# Main.net
KiCad netlist of a schematic drawn in Altium Designer
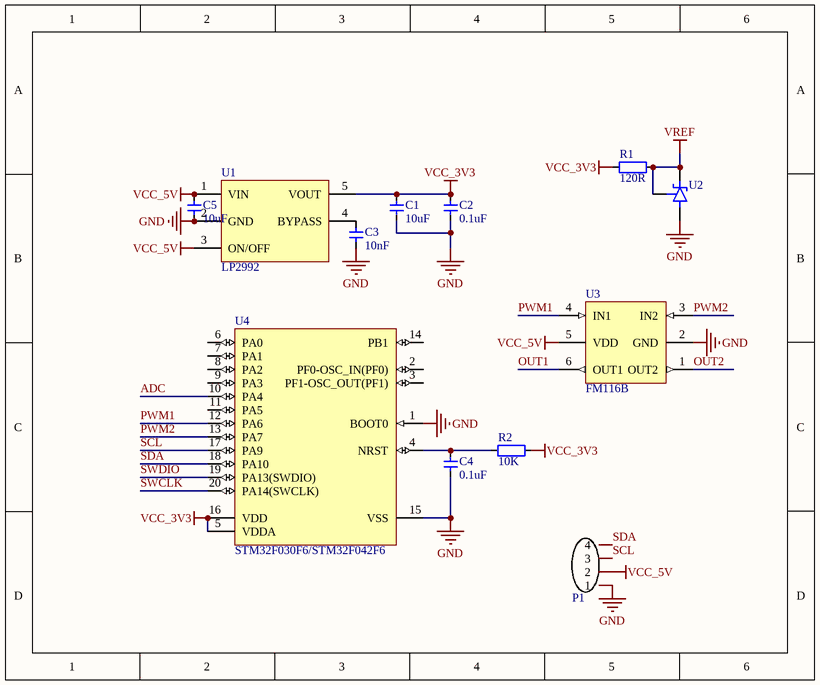
[diagram p0: Main.SchDoc]

(export (version "E")
  (design (tool "Eeschema 10.0.6"))
  (components
    (comp (ref "C1")
      (value "10uF")
      (footprint "ServoDrive:CAP_0402")
      (description "Capacitor")
      (libsource (lib "MyPcbLib") (part "电容-0402"))
    )
    (comp (ref "C2")
      (value "0.1uF")
      (footprint "ServoDrive:CAP_0402")
      (description "Capacitor")
      (libsource (lib "MyPcbLib") (part "电容-0402"))
    )
    (comp (ref "C3")
      (value "10nF")
      (footprint "ServoDrive:CAP_0402")
      (description "Capacitor")
      (libsource (lib "MyPcbLib") (part "电容-0402"))
    )
    (comp (ref "C4")
      (value "0.1uF")
      (footprint "ServoDrive:CAP_0402")
      (description "Capacitor")
      (libsource (lib "MyPcbLib") (part "电容-0402"))
    )
    (comp (ref "C5")
      (value "10uF")
      (footprint "ServoDrive:CAP_0402")
      (description "Capacitor")
      (libsource (lib "MyPcbLib") (part "电容-0402"))
    )
    (comp (ref "P1")
      (value "HDR1x4_1.27")
      (footprint "ServoDrive:HDR1X4_1.27_180")
      (description "Header")
      (libsource (lib "altium-import") (part "root_2_HDR1x4_1.27_"))
    )
    (comp (ref "R1")
      (value "120R")
      (footprint "ServoDrive:RES_0402")
      (description "Resistor")
      (libsource (lib "MyPcbLib") (part "电阻-0402"))
    )
    (comp (ref "R2")
      (value "10K")
      (footprint "ServoDrive:RES_0402")
      (description "Resistor")
      (libsource (lib "") (part "电阻-0402_1"))
    )
    (comp (ref "U1")
      (value "LP2992")
      (footprint "ServoDrive:SOT23-5")
      (description "LDO")
      (libsource (lib "MyPcbLib") (part "LP2992"))
    )
    (comp (ref "U2")
      (value "TL431IDBZT")
      (footprint "ServoDrive:SOT23-3")
      (description "Adjustable precision shunt regulator 3-SOT-23 -40 to 85")
      (fields (field (name "MF") "Texas Instruments"))
      (libsource (lib "MyPcbLib") (part "TL431IDBZT"))
    )
    (comp (ref "U3")
      (value "FM116B")
      (footprint "ServoDrive:SOT23-6")
      (fields (field (name "PARTNUMBER") "24LC256-I/ST"))
      (libsource (lib "MyPcbLib") (part "FM116B"))
    )
    (comp (ref "U4")
      (value "STM32F030F6/STM32F042F6")
      (footprint "ServoDrive:TSSOP-20")
      (fields (field (name "PARTNUMBER") "STM32F030F4P6"))
      (libsource (lib "MyPcbLib") (part "STM32F030F4P6"))
    )
  )
  (nets
    (net (code "1") (name "/ADC") (class "Default")
      (node (ref "U4") (pin "10") (pinfunction "PA4_10") (pintype "bidirectional"))
    )
    (net (code "2") (name "/OUT1") (class "Default")
      (node (ref "U3") (pin "6") (pinfunction "OUT1_6") (pintype "output"))
    )
    (net (code "3") (name "/OUT2") (class "Default")
      (node (ref "U3") (pin "1") (pinfunction "OUT2_1") (pintype "output"))
    )
    (net (code "4") (name "/PWM1") (class "Default")
      (node (ref "U3") (pin "4") (pinfunction "IN1_4") (pintype "input"))
      (node (ref "U4") (pin "12") (pinfunction "PA6_12") (pintype "bidirectional"))
    )
    (net (code "5") (name "/PWM2") (class "Default")
      (node (ref "U3") (pin "3") (pinfunction "IN2_3") (pintype "input"))
      (node (ref "U4") (pin "13") (pinfunction "PA7_13") (pintype "bidirectional"))
    )
    (net (code "6") (name "/SCL") (class "Default")
      (node (ref "P1") (pin "3") (pinfunction "3_3") (pintype "passive"))
      (node (ref "U4") (pin "17") (pinfunction "PA9_17") (pintype "bidirectional"))
    )
    (net (code "7") (name "/SDA") (class "Default")
      (node (ref "P1") (pin "4") (pinfunction "4_4") (pintype "passive"))
      (node (ref "U4") (pin "18") (pinfunction "PA10_18") (pintype "bidirectional"))
    )
    (net (code "8") (name "/SWCLK") (class "Default")
      (node (ref "U4") (pin "20") (pinfunction "PA14(SWCLK)_20") (pintype "bidirectional"))
    )
    (net (code "9") (name "/SWDIO") (class "Default")
      (node (ref "U4") (pin "19") (pinfunction "PA13(SWDIO)_19") (pintype "bidirectional"))
    )
    (net (code "10") (name "GND") (class "Default")
      (node (ref "C1") (pin "1") (pinfunction "1_1") (pintype "passive"))
      (node (ref "C2") (pin "1") (pinfunction "1_1") (pintype "passive"))
      (node (ref "C3") (pin "2") (pinfunction "2_2") (pintype "passive"))
      (node (ref "C4") (pin "1") (pinfunction "1_1") (pintype "passive"))
      (node (ref "C5") (pin "1") (pinfunction "1_1") (pintype "passive"))
      (node (ref "P1") (pin "1") (pinfunction "1_1") (pintype "passive"))
      (node (ref "U1") (pin "2") (pinfunction "GND_2") (pintype "passive"))
      (node (ref "U2") (pin "3") (pinfunction "ANODE_3") (pintype "passive"))
      (node (ref "U3") (pin "2") (pinfunction "GND_2") (pintype "power_in"))
      (node (ref "U4") (pin "1") (pinfunction "BOOT0_1") (pintype "input"))
      (node (ref "U4") (pin "15") (pinfunction "VSS_15") (pintype "power_in"))
    )
    (net (code "11") (name "Net-(U1-BYPASS)") (class "Default")
      (node (ref "C3") (pin "1") (pinfunction "1_1") (pintype "passive"))
      (node (ref "U1") (pin "4") (pinfunction "BYPASS_4") (pintype "passive"))
    )
    (net (code "12") (name "Net-(U4-NRST)") (class "Default")
      (node (ref "C4") (pin "2") (pinfunction "2_2") (pintype "passive"))
      (node (ref "R2") (pin "2") (pinfunction "2_2") (pintype "passive"))
      (node (ref "U4") (pin "4") (pinfunction "NRST_4") (pintype "bidirectional"))
    )
    (net (code "13") (name "VCC_3V3") (class "Default")
      (node (ref "C1") (pin "2") (pinfunction "2_2") (pintype "passive"))
      (node (ref "C2") (pin "2") (pinfunction "2_2") (pintype "passive"))
      (node (ref "R1") (pin "1") (pinfunction "1_1") (pintype "passive"))
      (node (ref "R2") (pin "1") (pinfunction "1_1") (pintype "passive"))
      (node (ref "U1") (pin "5") (pinfunction "VOUT_5") (pintype "passive"))
      (node (ref "U4") (pin "16") (pinfunction "VDD_16") (pintype "power_in"))
      (node (ref "U4") (pin "5") (pinfunction "VDDA_5") (pintype "power_in"))
    )
    (net (code "14") (name "VCC_5V") (class "Default")
      (node (ref "C5") (pin "2") (pinfunction "2_2") (pintype "passive"))
      (node (ref "P1") (pin "2") (pinfunction "2_2") (pintype "passive"))
      (node (ref "U1") (pin "1") (pinfunction "VIN_1") (pintype "passive"))
      (node (ref "U1") (pin "3") (pinfunction "ON/OFF_3") (pintype "passive"))
      (node (ref "U3") (pin "5") (pinfunction "VDD_5") (pintype "power_in"))
    )
    (net (code "15") (name "VREF") (class "Default")
      (node (ref "R1") (pin "2") (pinfunction "2_2") (pintype "passive"))
      (node (ref "U2") (pin "1") (pinfunction "CATHODE_1") (pintype "passive"))
      (node (ref "U2") (pin "2") (pinfunction "REF_2") (pintype "passive"))
    )
    (net (code "16") (name "unconnected-(U4-PA0-Pad6)") (class "Default")
      (node (ref "U4") (pin "6") (pinfunction "PA0_6") (pintype "bidirectional"))
    )
    (net (code "17") (name "unconnected-(U4-PA1-Pad7)") (class "Default")
      (node (ref "U4") (pin "7") (pinfunction "PA1_7") (pintype "bidirectional"))
    )
    (net (code "18") (name "unconnected-(U4-PA2-Pad8)") (class "Default")
      (node (ref "U4") (pin "8") (pinfunction "PA2_8") (pintype "bidirectional"))
    )
    (net (code "19") (name "unconnected-(U4-PA3-Pad9)") (class "Default")
      (node (ref "U4") (pin "9") (pinfunction "PA3_9") (pintype "bidirectional"))
    )
    (net (code "20") (name "unconnected-(U4-PA5-Pad11)") (class "Default")
      (node (ref "U4") (pin "11") (pinfunction "PA5_11") (pintype "bidirectional"))
    )
    (net (code "21") (name "unconnected-(U4-PB1-Pad14)") (class "Default")
      (node (ref "U4") (pin "14") (pinfunction "PB1_14") (pintype "bidirectional"))
    )
    (net (code "22") (name "unconnected-(U4-PF0-OSC_IN(PF0)-Pad2)") (class "Default")
      (node (ref "U4") (pin "2") (pinfunction "PF0-OSC_IN(PF0)_2") (pintype "bidirectional"))
    )
    (net (code "23") (name "unconnected-(U4-PF1-OSC_OUT(PF1)-Pad3)") (class "Default")
      (node (ref "U4") (pin "3") (pinfunction "PF1-OSC_OUT(PF1)_3") (pintype "bidirectional"))
    )
  )
)
